# ATMEGA32U4-AU.net
KiCad netlist of a schematic drawn in Altium Designer
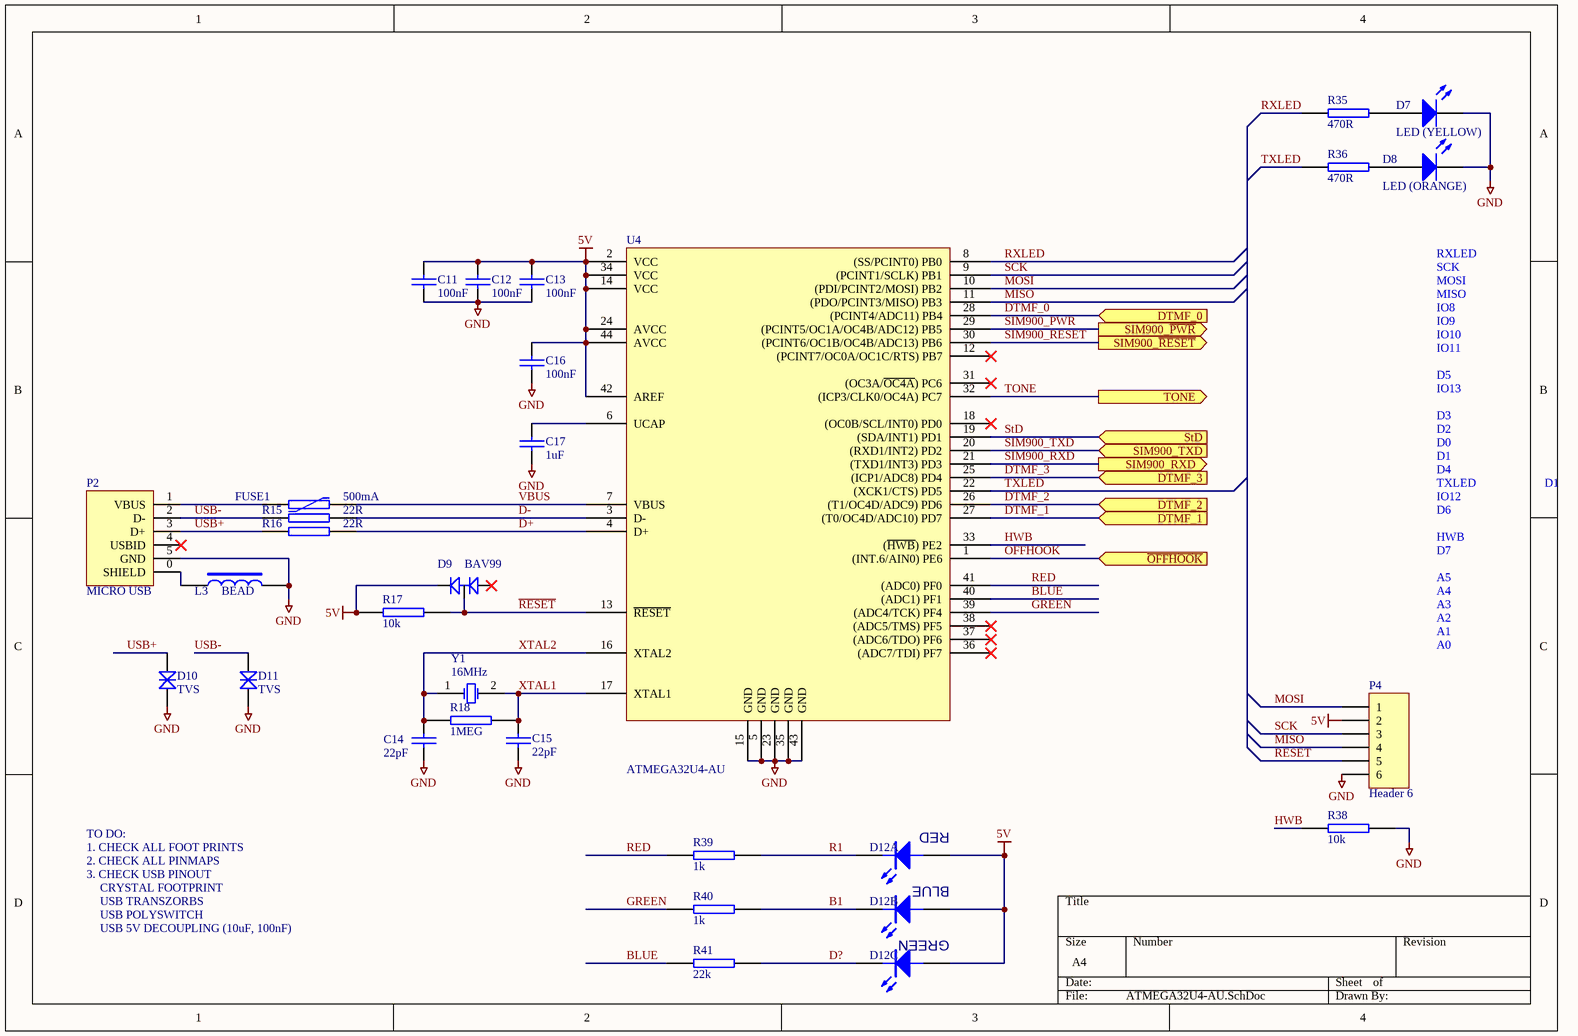
[diagram p0: ATMEGA32U4-AU.SchDoc]

(export (version "E")
  (design (tool "Eeschema 10.0.6"))
  (components
    (comp (ref "C11")
      (value "100nF")
      (footprint "CAP (3D) - 0603")
      (description "CAPACITOR SMD 0603")
      (fields
        (field (name "MOUSER PART NO.") "81-GCM188R71C104KA7D")
        (field (name "FARNELL PART NO.") "1414610")
      )
      (libsource (lib "NASCO Capacitors") (part "CAP SMD 0603 100nF"))
    )
    (comp (ref "C12")
      (value "100nF")
      (footprint "CAP (3D) - 0603")
      (description "CAPACITOR SMD 0603")
      (fields
        (field (name "MOUSER PART NO.") "81-GCM188R71C104KA7D")
        (field (name "FARNELL PART NO.") "1414610")
      )
      (libsource (lib "NASCO Capacitors") (part "CAP SMD 0603 100nF"))
    )
    (comp (ref "C13")
      (value "100nF")
      (footprint "CAP (3D) - 0603")
      (description "CAPACITOR SMD 0603")
      (fields
        (field (name "MOUSER PART NO.") "81-GCM188R71C104KA7D")
        (field (name "FARNELL PART NO.") "1414610")
      )
      (libsource (lib "NASCO Capacitors") (part "CAP SMD 0603 100nF"))
    )
    (comp (ref "C14")
      (value "22pF")
      (footprint "CAP (3D) - 0603")
      (description "CAPACITOR SMD 0603")
      (libsource (lib "NASCO Capacitors") (part "CAP SMD 0603 1nF"))
    )
    (comp (ref "C15")
      (value "22pF")
      (footprint "CAP (3D) - 0603")
      (description "CAPACITOR SMD 0603")
      (libsource (lib "NASCO Capacitors") (part "CAP SMD 0603 1nF"))
    )
    (comp (ref "C16")
      (value "100nF")
      (footprint "CAP (3D) - 0603")
      (description "CAPACITOR SMD 0603")
      (fields
        (field (name "MOUSER PART NO.") "81-GCM188R71C104KA7D")
        (field (name "FARNELL PART NO.") "1414610")
      )
      (libsource (lib "NASCO Capacitors") (part "CAP SMD 0603 100nF"))
    )
    (comp (ref "C17")
      (value "1uF")
      (footprint "CAP (3D) - 0805")
      (description "CAPACITOR SMD 0805")
      (fields (field (name "MOUSER PART NO.") "80-C0805S103K5R"))
      (libsource (lib "NASCO Capacitors") (part "CAP SMD 0805 1uF"))
    )
    (comp (ref "D7")
      (value "LED (YELLOW)")
      (footprint "LED(3D) YELLOW - 0805")
      (description "LED 0805 YELLOW")
      (libsource (lib "NASCO") (part "LED 0805 YELLOW"))
    )
    (comp (ref "D8")
      (value "LED (ORANGE)")
      (footprint "LED(3D) ORANGE - 0805")
      (description "LED 0805 ORANGE")
      (libsource (lib "NASCO") (part "LED 0805 ORANGE"))
    )
    (comp (ref "D9")
      (value "BAV99")
      (footprint "SOT23-3L")
      (description "DUAL DIODE, BAV99")
      (fields (field (name "MOUSER PART NO.") "771-BAV99/T3") (field (name "FARNELL PART NO.") "9843612"))
      (libsource (lib "NASCO") (part "BAV99"))
    )
    (comp (ref "D10")
      (value "TVS")
      (footprint "TVS (3D) - 0603")
      (description "Transient Voltage Suppression (TVS) Diode")
      (fields (field (name "MANUFACTURER PART NO.") "CG0603MLC-05E"))
      (libsource (lib "SIM900") (part "TVS DIODE"))
    )
    (comp (ref "D11")
      (value "TVS")
      (footprint "TVS (3D) - 0603")
      (description "Transient Voltage Suppression (TVS) Diode")
      (fields (field (name "MANUFACTURER PART NO.") "CG0603MLC-05E"))
      (libsource (lib "SIM900") (part "TVS DIODE"))
    )
    (comp (ref "D12")
      (value "RGB 5mm")
      (footprint "LED(3D) 5MM VERTICAL (RGB) - COMMON ANODE")
      (libsource (lib "call point") (part "RGB_5mm"))
    )
    (comp (ref "FUSE1")
      (value "500mA")
      (footprint "miniSMD Polyswitch")
      (description "POLYSWITCH 500mA 1812")
      (fields (field (name "MOUSER PART NO.") "PTS181216V050"))
      (libsource (lib "SIM900") (part "POLYSWITCH 500mA 1812"))
    )
    (comp (ref "L3")
      (value "BEAD")
      (footprint "RES (3D) - 1210")
      (description "INDUCTOR SMD 1210")
      (fields (field (name "MANUFACTURER PART NO.") "2512063007Y3"))
      (libsource (lib "NASCO") (part "INDUCTOR SMD 1210 100uH"))
    )
    (comp (ref "P2")
      (value "MICRO USB")
      (footprint "MICRO USB")
      (libsource (lib "SIM900") (part "MICRO USB"))
    )
    (comp (ref "P4")
      (value "Header 6")
      (footprint "HDR2X3 (3D)")
      (description "Header, 6-Pin")
      (fields (field (name "PUBLISHER") "Altium Limited"))
      (libsource (lib "Miscellaneous Connectors") (part "Header 6"))
    )
    (comp (ref "R15")
      (value "22R")
      (footprint "RES (3D) - 0603")
      (description "RESISTOR SMD 0603 0R")
      (libsource (lib "NASCO Resistors") (part "RES SMD 0603 0R"))
    )
    (comp (ref "R16")
      (value "22R")
      (footprint "RES (3D) - 0603")
      (description "RESISTOR SMD 0603 0R")
      (libsource (lib "NASCO Resistors") (part "RES SMD 0603 0R"))
    )
    (comp (ref "R17")
      (value "10k")
      (footprint "RES (3D) - 0603")
      (description "RESISTOR SMD 0603 10k")
      (fields (field (name "MOUSER PART NO.") "652-CR0603FX-1002ELF") (field (name "MANUFACTURER") "Bourns"))
      (libsource (lib "NASCO Resistors") (part "RES SMD 0603 10k"))
    )
    (comp (ref "R18")
      (value "1MEG")
      (footprint "RES (3D) - 0603")
      (description "RESISTOR SMD 0603 0R")
      (libsource (lib "NASCO Resistors") (part "RES SMD 0603 0R"))
    )
    (comp (ref "R35")
      (value "470R")
      (footprint "RES (3D) - 0603")
      (description "RESISTOR SMD 0603 590R")
      (libsource (lib "NASCO Resistors") (part "RES SMD 0603 590R"))
    )
    (comp (ref "R36")
      (value "470R")
      (footprint "RES (3D) - 0603")
      (description "RESISTOR SMD 0603 590R")
      (libsource (lib "NASCO Resistors") (part "RES SMD 0603 590R"))
    )
    (comp (ref "R38")
      (value "10k")
      (footprint "RES (3D) - 0603")
      (description "RESISTOR SMD 0603 10k")
      (fields (field (name "MOUSER PART NO.") "652-CR0603FX-1002ELF") (field (name "MANUFACTURER") "Bourns"))
      (libsource (lib "NASCO Resistors") (part "RES SMD 0603 10k"))
    )
    (comp (ref "R39")
      (value "1k")
      (footprint "RES (3D) - 0603")
      (description "RESISTOR SMD 0603")
      (fields
        (field (name "MOUSER PART NO.") "652-CR0603-JW-102ELF")
        (field (name "FARNELL PART NO.") "9331700")
      )
      (libsource (lib "NASCO Resistors") (part "RES SMD 0603 10k"))
    )
    (comp (ref "R40")
      (value "1k")
      (footprint "RES (3D) - 0603")
      (description "RESISTOR SMD 0603")
      (fields
        (field (name "MOUSER PART NO.") "652-CR0603-JW-102ELF")
        (field (name "FARNELL PART NO.") "9331700")
      )
      (libsource (lib "NASCO Resistors") (part "RES SMD 0603 10k"))
    )
    (comp (ref "R41")
      (value "22k")
      (footprint "RES (3D) - 0603")
      (description "RESISTOR SMD 0603")
      (fields (field (name "MOUSER PART NO.") "652-CR0603FX-4223ELF") (field (name "MANUFACTURER") "Bourns"))
      (libsource (lib "NASCO Resistors") (part "RES SMD 0603 10k"))
    )
    (comp (ref "U4")
      (value "ATMEGA32U4-AU")
      (footprint "TQFP44")
      (fields (field (name "MOUSER PART NO.") "556-ATMEGA32U4-AU"))
      (libsource (lib "SIM900") (part "ATmega32U4"))
    )
    (comp (ref "Y1")
      (value "16MHz")
      (footprint "HC49/4H_SMX")
      (description "Crystal Oscillator")
      (fields (field (name "MOUSER PART NO.") "520-CSM1600-20-X"))
      (libsource (lib "Miscellaneous Devices") (part "XTAL"))
    )
  )
  (nets
    (net (code "1") (name "/B1") (class "Default")
      (node (ref "D12") (pin "4") (pinfunction "K_4") (pintype "passive"))
      (node (ref "R40") (pin "2") (pinfunction "2_2") (pintype "passive"))
    )
    (net (code "2") (name "/BLUE") (class "Default")
      (node (ref "R41") (pin "1") (pinfunction "1_1") (pintype "passive"))
      (node (ref "U4") (pin "40") (pinfunction "(ADC1)_PF1_40") (pintype "passive"))
    )
    (net (code "3") (name "/D+") (class "Default")
      (node (ref "R16") (pin "2") (pinfunction "2_2") (pintype "passive"))
      (node (ref "U4") (pin "4") (pinfunction "D+_4") (pintype "passive"))
    )
    (net (code "4") (name "/D-") (class "Default")
      (node (ref "R15") (pin "2") (pinfunction "2_2") (pintype "passive"))
      (node (ref "U4") (pin "3") (pinfunction "D-_3") (pintype "passive"))
    )
    (net (code "5") (name "/D?") (class "Default")
      (node (ref "D12") (pin "3") (pinfunction "K_3") (pintype "passive"))
      (node (ref "R41") (pin "2") (pinfunction "2_2") (pintype "passive"))
    )
    (net (code "6") (name "/DTMF_0") (class "Default")
      (node (ref "U4") (pin "28") (pinfunction "(PCINT4/ADC11)_PB4_28") (pintype "passive"))
    )
    (net (code "7") (name "/DTMF_1") (class "Default")
      (node (ref "U4") (pin "27") (pinfunction "(T0/OC4D/ADC10)_PD7_27") (pintype "passive"))
    )
    (net (code "8") (name "/DTMF_2") (class "Default")
      (node (ref "U4") (pin "26") (pinfunction "(T1/OC4D/ADC9)_PD6_26") (pintype "passive"))
    )
    (net (code "9") (name "/DTMF_3") (class "Default")
      (node (ref "U4") (pin "25") (pinfunction "(ICP1/ADC8)_PD4_25") (pintype "passive"))
    )
    (net (code "10") (name "/GREEN") (class "Default")
      (node (ref "R40") (pin "1") (pinfunction "1_1") (pintype "passive"))
      (node (ref "U4") (pin "39") (pinfunction "(ADC4/TCK)_PF4_39") (pintype "passive"))
    )
    (net (code "11") (name "/HWB") (class "Default")
      (node (ref "R38") (pin "2") (pinfunction "2_2") (pintype "passive"))
      (node (ref "U4") (pin "33") (pinfunction "(~{HWB})_PE2_33") (pintype "passive"))
    )
    (net (code "12") (name "/MISO") (class "Default")
      (node (ref "P4") (pin "4") (pinfunction "4_4") (pintype "passive"))
      (node (ref "U4") (pin "11") (pinfunction "(PDO/PCINT3/MISO)_PB3_11") (pintype "passive"))
    )
    (net (code "13") (name "/MOSI") (class "Default")
      (node (ref "P4") (pin "1") (pinfunction "1_1") (pintype "passive"))
      (node (ref "U4") (pin "10") (pinfunction "(PDI/PCINT2/MOSI)_PB2_10") (pintype "passive"))
    )
    (net (code "14") (name "/R1") (class "Default")
      (node (ref "D12") (pin "1") (pinfunction "K_1") (pintype "passive"))
      (node (ref "R39") (pin "2") (pinfunction "2_2") (pintype "passive"))
    )
    (net (code "15") (name "/RED") (class "Default")
      (node (ref "R39") (pin "1") (pinfunction "1_1") (pintype "passive"))
      (node (ref "U4") (pin "41") (pinfunction "(ADC0)_PF0_41") (pintype "passive"))
    )
    (net (code "16") (name "/RXLED") (class "Default")
      (node (ref "R35") (pin "1") (pinfunction "1_1") (pintype "passive"))
      (node (ref "U4") (pin "8") (pinfunction "(SS/PCINT0)_PB0_8") (pintype "passive"))
    )
    (net (code "17") (name "/SCK") (class "Default")
      (node (ref "P4") (pin "3") (pinfunction "3_3") (pintype "passive"))
      (node (ref "U4") (pin "9") (pinfunction "(PCINT1/SCLK)_PB1_9") (pintype "passive"))
    )
    (net (code "18") (name "/SIM900_RXD") (class "Default")
      (node (ref "U4") (pin "21") (pinfunction "(TXD1/INT3)_PD3_21") (pintype "passive"))
    )
    (net (code "19") (name "/SIM900_TXD") (class "Default")
      (node (ref "U4") (pin "20") (pinfunction "(RXD1/INT2)_PD2_20") (pintype "passive"))
    )
    (net (code "20") (name "/SIM900_~{PWR}") (class "Default")
      (node (ref "U4") (pin "29") (pinfunction "(PCINT5/OC1A/OC4B/ADC12)_PB5_29") (pintype "passive"))
    )
    (net (code "21") (name "/SIM900_~{RESET}") (class "Default")
      (node (ref "U4") (pin "30") (pinfunction "(PCINT6/OC1B/OC4B/ADC13)_PB6_30") (pintype "passive"))
    )
    (net (code "22") (name "/StD") (class "Default")
      (node (ref "U4") (pin "19") (pinfunction "(SDA/INT1)_PD1_19") (pintype "passive"))
    )
    (net (code "23") (name "/TONE") (class "Default")
      (node (ref "U4") (pin "32") (pinfunction "(ICP3/CLK0/OC4A)_PC7_32") (pintype "passive"))
    )
    (net (code "24") (name "/TXLED") (class "Default")
      (node (ref "R36") (pin "1") (pinfunction "1_1") (pintype "passive"))
      (node (ref "U4") (pin "22") (pinfunction "(XCK1/CTS)_PD5_22") (pintype "passive"))
    )
    (net (code "25") (name "/USB+") (class "Default")
      (node (ref "D10") (pin "2") (pinfunction "K_2") (pintype "passive"))
      (node (ref "P2") (pin "3") (pinfunction "D+_3") (pintype "passive"))
      (node (ref "R16") (pin "1") (pinfunction "1_1") (pintype "passive"))
    )
    (net (code "26") (name "/USB-") (class "Default")
      (node (ref "D11") (pin "2") (pinfunction "K_2") (pintype "passive"))
      (node (ref "P2") (pin "2") (pinfunction "D-_2") (pintype "passive"))
      (node (ref "R15") (pin "1") (pinfunction "1_1") (pintype "passive"))
    )
    (net (code "27") (name "/VBUS") (class "Default")
      (node (ref "FUSE1") (pin "2") (pinfunction "2_2") (pintype "passive"))
      (node (ref "U4") (pin "7") (pinfunction "VBUS_7") (pintype "passive"))
    )
    (net (code "28") (name "/XTAL1") (class "Default")
      (node (ref "C15") (pin "1") (pinfunction "1_1") (pintype "passive"))
      (node (ref "R18") (pin "2") (pinfunction "2_2") (pintype "passive"))
      (node (ref "U4") (pin "17") (pinfunction "XTAL1_17") (pintype "passive"))
      (node (ref "Y1") (pin "2") (pinfunction "OSC2_2") (pintype "passive"))
    )
    (net (code "29") (name "/XTAL2") (class "Default")
      (node (ref "C14") (pin "1") (pinfunction "1_1") (pintype "passive"))
      (node (ref "R18") (pin "1") (pinfunction "1_1") (pintype "passive"))
      (node (ref "U4") (pin "16") (pinfunction "XTAL2_16") (pintype "passive"))
      (node (ref "Y1") (pin "1") (pinfunction "OSC1_1") (pintype "passive"))
    )
    (net (code "30") (name "/~{OFFHOOK}") (class "Default")
      (node (ref "U4") (pin "1") (pinfunction "(INT.6/AIN0)_PE6_1") (pintype "passive"))
    )
    (net (code "31") (name "/~{RESET}") (class "Default")
      (node (ref "D9") (pin "3") (pinfunction "C1/A2_3") (pintype "passive"))
      (node (ref "P4") (pin "5") (pinfunction "5_5") (pintype "passive"))
      (node (ref "R17") (pin "1") (pinfunction "1_1") (pintype "passive"))
      (node (ref "U4") (pin "13") (pinfunction "~{RESET}_13") (pintype "passive"))
    )
    (net (code "32") (name "5V") (class "Default")
      (node (ref "C11") (pin "1") (pinfunction "1_1") (pintype "passive"))
      (node (ref "C12") (pin "1") (pinfunction "1_1") (pintype "passive"))
      (node (ref "C13") (pin "1") (pinfunction "1_1") (pintype "passive"))
      (node (ref "C16") (pin "1") (pinfunction "1_1") (pintype "passive"))
      (node (ref "D12") (pin "2") (pinfunction "A_2") (pintype "passive"))
      (node (ref "D9") (pin "2") (pinfunction "C2_2") (pintype "passive"))
      (node (ref "P4") (pin "2") (pinfunction "2_2") (pintype "passive"))
      (node (ref "R17") (pin "2") (pinfunction "2_2") (pintype "passive"))
      (node (ref "U4") (pin "14") (pinfunction "VCC_14") (pintype "passive"))
      (node (ref "U4") (pin "2") (pinfunction "VCC_2") (pintype "passive"))
      (node (ref "U4") (pin "24") (pinfunction "AVCC_24") (pintype "passive"))
      (node (ref "U4") (pin "34") (pinfunction "VCC_34") (pintype "passive"))
      (node (ref "U4") (pin "42") (pinfunction "AREF_42") (pintype "passive"))
      (node (ref "U4") (pin "44") (pinfunction "AVCC_44") (pintype "passive"))
    )
    (net (code "33") (name "GND") (class "Default")
      (node (ref "C11") (pin "2") (pinfunction "2_2") (pintype "passive"))
      (node (ref "C12") (pin "2") (pinfunction "2_2") (pintype "passive"))
      (node (ref "C13") (pin "2") (pinfunction "2_2") (pintype "passive"))
      (node (ref "C14") (pin "2") (pinfunction "2_2") (pintype "passive"))
      (node (ref "C15") (pin "2") (pinfunction "2_2") (pintype "passive"))
      (node (ref "C16") (pin "2") (pinfunction "2_2") (pintype "passive"))
      (node (ref "C17") (pin "2") (pinfunction "2_2") (pintype "passive"))
      (node (ref "D10") (pin "1") (pinfunction "A_1") (pintype "passive"))
      (node (ref "D11") (pin "1") (pinfunction "A_1") (pintype "passive"))
      (node (ref "D7") (pin "2") (pinfunction "K_2") (pintype "passive"))
      (node (ref "D8") (pin "2") (pinfunction "K_2") (pintype "passive"))
      (node (ref "L3") (pin "2") (pinfunction "2_2") (pintype "passive"))
      (node (ref "P2") (pin "5") (pinfunction "GND_5") (pintype "passive"))
      (node (ref "P4") (pin "6") (pinfunction "6_6") (pintype "passive"))
      (node (ref "R38") (pin "1") (pinfunction "1_1") (pintype "passive"))
      (node (ref "U4") (pin "15") (pinfunction "GND_15") (pintype "passive"))
      (node (ref "U4") (pin "23") (pinfunction "GND_23") (pintype "passive"))
      (node (ref "U4") (pin "35") (pinfunction "GND_35") (pintype "passive"))
      (node (ref "U4") (pin "43") (pinfunction "GND_43") (pintype "passive"))
      (node (ref "U4") (pin "5") (pinfunction "GND_5") (pintype "passive"))
    )
    (net (code "34") (name "Net-(D7-A)") (class "Default")
      (node (ref "D7") (pin "1") (pinfunction "A_1") (pintype "passive"))
      (node (ref "R35") (pin "2") (pinfunction "2_2") (pintype "passive"))
    )
    (net (code "35") (name "Net-(D8-A)") (class "Default")
      (node (ref "D8") (pin "1") (pinfunction "A_1") (pintype "passive"))
      (node (ref "R36") (pin "2") (pinfunction "2_2") (pintype "passive"))
    )
    (net (code "36") (name "Net-(P2-SHIELD)") (class "Default")
      (node (ref "L3") (pin "1") (pinfunction "1_1") (pintype "passive"))
      (node (ref "P2") (pin "0") (pinfunction "SHIELD_0") (pintype "passive"))
    )
    (net (code "37") (name "Net-(P2-VBUS)") (class "Default")
      (node (ref "FUSE1") (pin "1") (pinfunction "1_1") (pintype "passive"))
      (node (ref "P2") (pin "1") (pinfunction "VBUS_1") (pintype "passive"))
    )
    (net (code "38") (name "Net-(U4-UCAP)") (class "Default")
      (node (ref "C17") (pin "1") (pinfunction "1_1") (pintype "passive"))
      (node (ref "U4") (pin "6") (pinfunction "UCAP_6") (pintype "passive"))
    )
    (net (code "39") (name "unconnected-(D9-A1-Pad1)") (class "Default")
      (node (ref "D9") (pin "1") (pinfunction "A1_1") (pintype "passive+no_connect"))
    )
    (net (code "40") (name "unconnected-(P2-USBID-Pad4)") (class "Default")
      (node (ref "P2") (pin "4") (pinfunction "USBID_4") (pintype "passive+no_connect"))
    )
    (net (code "41") (name "unconnected-(U4-(ADC5{slash}TMS)_PF5-Pad38)") (class "Default")
      (node (ref "U4") (pin "38") (pinfunction "(ADC5/TMS)_PF5_38") (pintype "passive+no_connect"))
    )
    (net (code "42") (name "unconnected-(U4-(ADC6{slash}TDO)_PF6-Pad37)") (class "Default")
      (node (ref "U4") (pin "37") (pinfunction "(ADC6/TDO)_PF6_37") (pintype "passive+no_connect"))
    )
    (net (code "43") (name "unconnected-(U4-(ADC7{slash}TDI)_PF7-Pad36)") (class "Default")
      (node (ref "U4") (pin "36") (pinfunction "(ADC7/TDI)_PF7_36") (pintype "passive+no_connect"))
    )
    (net (code "44") (name "unconnected-(U4-(OC0B{slash}SCL{slash}INT0)_PD0-Pad18)") (class "Default")
      (node (ref "U4") (pin "18") (pinfunction "(OC0B/SCL/INT0)_PD0_18") (pintype "passive+no_connect"))
    )
    (net (code "45") (name "unconnected-(U4-(OC3A{slash}~{OC4A})_PC6-Pad31)") (class "Default")
      (node (ref "U4") (pin "31") (pinfunction "(OC3A/~{OC4A})_PC6_31") (pintype "passive+no_connect"))
    )
    (net (code "46") (name "unconnected-(U4-(PCINT7{slash}OC0A{slash}OC1C{slash}RTS)_PB7-Pad12)") (class "Default")
      (node (ref "U4") (pin "12") (pinfunction "(PCINT7/OC0A/OC1C/RTS)_PB7_12") (pintype "passive+no_connect"))
    )
  )
)
